# driver.net
KiCad netlist of a schematic drawn in EAGLE
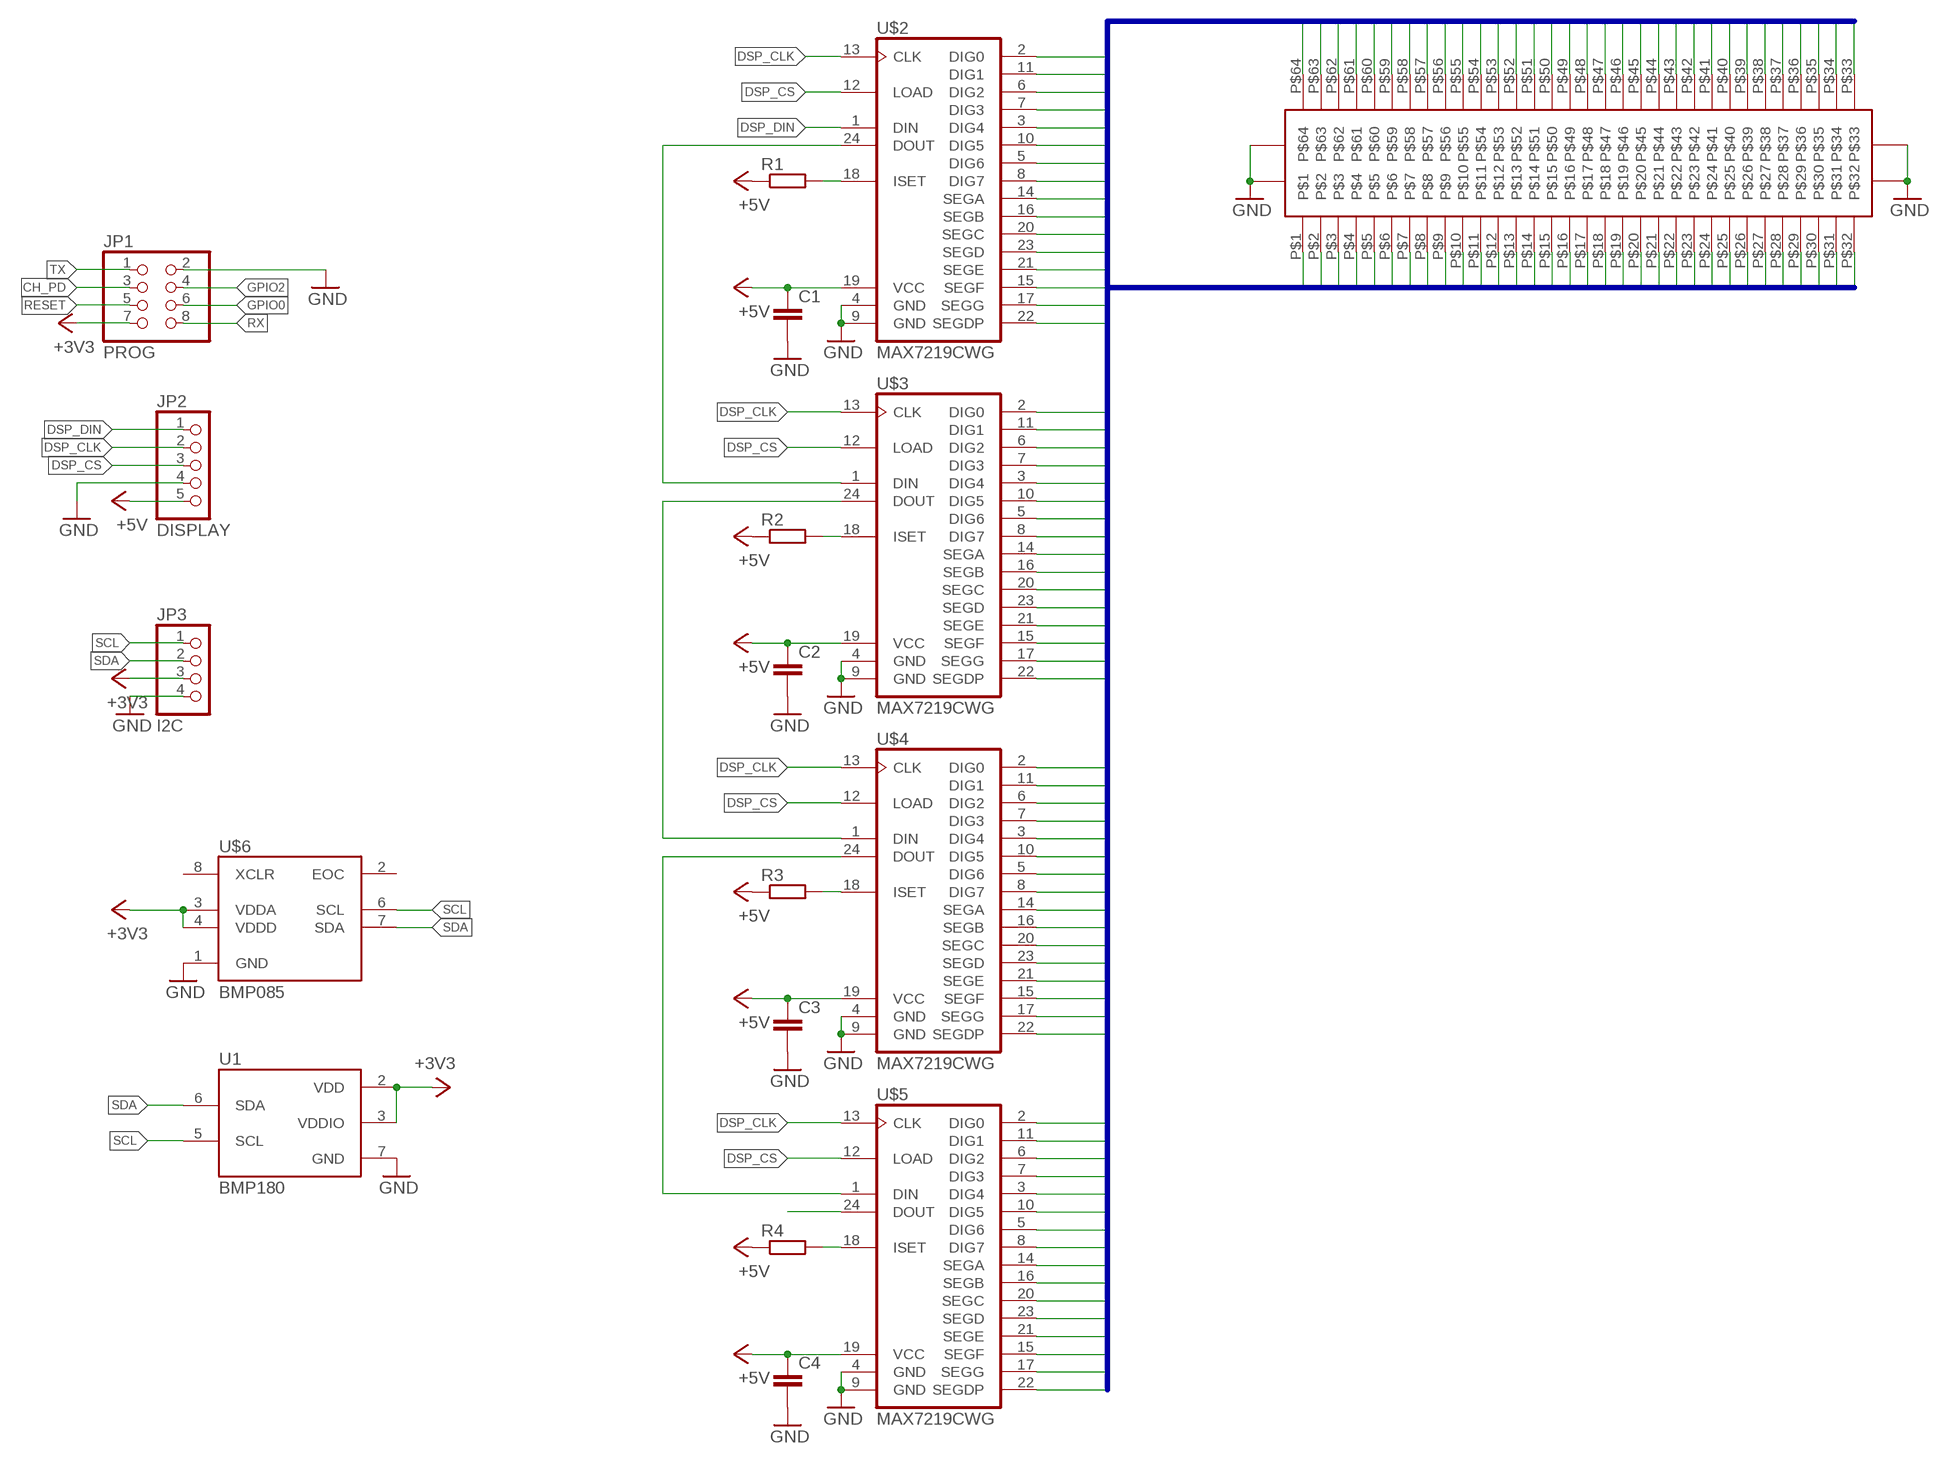
[diagram p0: schematic, sheet 1]

(export (version "E")
  (design (tool "Eeschema 10.0.6"))
  (components
    (comp (ref "C1")
      (value "C-EUC0805")
      (footprint "eagle-import:C0805")
      (libsource (lib "eagle-import") (part "C-EUC0805"))
    )
    (comp (ref "C2")
      (value "C-EUC0805")
      (footprint "eagle-import:C0805")
      (libsource (lib "eagle-import") (part "C-EUC0805"))
    )
    (comp (ref "C3")
      (value "C-EUC0805")
      (footprint "eagle-import:C0805")
      (libsource (lib "eagle-import") (part "C-EUC0805"))
    )
    (comp (ref "C4")
      (value "C-EUC0805")
      (footprint "eagle-import:C0805")
      (libsource (lib "eagle-import") (part "C-EUC0805"))
    )
    (comp (ref "JP1")
      (value "PROG")
      (footprint "eagle-import:2X04")
      (libsource (lib "eagle-import") (part "PINHD-2X4"))
    )
    (comp (ref "JP2")
      (value "DISPLAY")
      (footprint "eagle-import:1X05")
      (libsource (lib "eagle-import") (part "PINHD-1X5"))
    )
    (comp (ref "JP3")
      (value "I2C")
      (footprint "eagle-import:1X04")
      (libsource (lib "eagle-import") (part "PINHD-1X4"))
    )
    (comp (ref "R1")
      (value "R-EU_R0805")
      (footprint "eagle-import:R0805")
      (libsource (lib "eagle-import") (part "R-EU_R0805"))
    )
    (comp (ref "R2")
      (value "R-EU_R0805")
      (footprint "eagle-import:R0805")
      (libsource (lib "eagle-import") (part "R-EU_R0805"))
    )
    (comp (ref "R3")
      (value "R-EU_R0805")
      (footprint "eagle-import:R0805")
      (libsource (lib "eagle-import") (part "R-EU_R0805"))
    )
    (comp (ref "R4")
      (value "R-EU_R0805")
      (footprint "eagle-import:R0805")
      (libsource (lib "eagle-import") (part "R-EU_R0805"))
    )
    (comp (ref "U$1")
      (value "ANGLE_BOARD_CONNECTORTWO_SIDED")
      (footprint "eagle-import:TWO_SIDED")
      (libsource (lib "eagle-import") (part "ANGLE_BOARD_CONNECTORTWO_SIDED"))
    )
    (comp (ref "U$2")
      (value "MAX7219CWG")
      (footprint "eagle-import:SO24L")
      (libsource (lib "eagle-import") (part "MAX7219CWG"))
    )
    (comp (ref "U$3")
      (value "MAX7219CWG")
      (footprint "eagle-import:SO24L")
      (libsource (lib "eagle-import") (part "MAX7219CWG"))
    )
    (comp (ref "U$4")
      (value "MAX7219CWG")
      (footprint "eagle-import:SO24L")
      (libsource (lib "eagle-import") (part "MAX7219CWG"))
    )
    (comp (ref "U$5")
      (value "MAX7219CWG")
      (footprint "eagle-import:SO24L")
      (libsource (lib "eagle-import") (part "MAX7219CWG"))
    )
    (comp (ref "U$6")
      (value "BMP085")
      (footprint "eagle-import:BMP085")
      (libsource (lib "eagle-import") (part "BMP085"))
    )
    (comp (ref "U1")
      (value "BMP180")
      (footprint "eagle-import:BMP180")
      (libsource (lib "eagle-import") (part "BMP180"))
    )
  )
  (nets
    (net (code "1") (name "+3V3") (class "Default")
      (node (ref "JP1") (pin "7") (pinfunction "7_7") (pintype "passive"))
      (node (ref "JP3") (pin "3") (pinfunction "3_3") (pintype "passive"))
      (node (ref "U$6") (pin "3") (pinfunction "VDDA_3") (pintype "power_in"))
      (node (ref "U$6") (pin "4") (pinfunction "VDDD_4") (pintype "power_in"))
      (node (ref "U1") (pin "2") (pinfunction "VDD_2") (pintype "power_in"))
      (node (ref "U1") (pin "3") (pinfunction "VDDIO_3") (pintype "power_in"))
    )
    (net (code "2") (name "+5V") (class "Default")
      (node (ref "C1") (pin "1") (pinfunction "1_1") (pintype "passive"))
      (node (ref "C2") (pin "1") (pinfunction "1_1") (pintype "passive"))
      (node (ref "C3") (pin "1") (pinfunction "1_1") (pintype "passive"))
      (node (ref "C4") (pin "1") (pinfunction "1_1") (pintype "passive"))
      (node (ref "JP2") (pin "5") (pinfunction "5_5") (pintype "passive"))
      (node (ref "R1") (pin "1") (pinfunction "1_1") (pintype "passive"))
      (node (ref "R2") (pin "1") (pinfunction "1_1") (pintype "passive"))
      (node (ref "R3") (pin "1") (pinfunction "1_1") (pintype "passive"))
      (node (ref "R4") (pin "1") (pinfunction "1_1") (pintype "passive"))
      (node (ref "U$2") (pin "19") (pinfunction "VCC_19") (pintype "power_in"))
      (node (ref "U$3") (pin "19") (pinfunction "VCC_19") (pintype "power_in"))
      (node (ref "U$4") (pin "19") (pinfunction "VCC_19") (pintype "power_in"))
      (node (ref "U$5") (pin "19") (pinfunction "VCC_19") (pintype "power_in"))
    )
    (net (code "3") (name "/M1C1") (class "Default")
      (node (ref "U$1") (pin "P$64") (pinfunction "P$64_P$64") (pintype "bidirectional"))
      (node (ref "U$2") (pin "2") (pinfunction "DIG0_2") (pintype "output"))
    )
    (net (code "4") (name "/M1C2") (class "Default")
      (node (ref "U$1") (pin "P$63") (pinfunction "P$63_P$63") (pintype "bidirectional"))
      (node (ref "U$2") (pin "11") (pinfunction "DIG1_11") (pintype "output"))
    )
    (net (code "5") (name "/M1C3") (class "Default")
      (node (ref "U$1") (pin "P$62") (pinfunction "P$62_P$62") (pintype "bidirectional"))
      (node (ref "U$2") (pin "6") (pinfunction "DIG2_6") (pintype "output"))
    )
    (net (code "6") (name "/M1C4") (class "Default")
      (node (ref "U$1") (pin "P$61") (pinfunction "P$61_P$61") (pintype "bidirectional"))
      (node (ref "U$2") (pin "7") (pinfunction "DIG3_7") (pintype "output"))
    )
    (net (code "7") (name "/M1C5") (class "Default")
      (node (ref "U$1") (pin "P$60") (pinfunction "P$60_P$60") (pintype "bidirectional"))
      (node (ref "U$2") (pin "3") (pinfunction "DIG4_3") (pintype "output"))
    )
    (net (code "8") (name "/M1C6") (class "Default")
      (node (ref "U$1") (pin "P$59") (pinfunction "P$59_P$59") (pintype "bidirectional"))
      (node (ref "U$2") (pin "10") (pinfunction "DIG5_10") (pintype "output"))
    )
    (net (code "9") (name "/M1C7") (class "Default")
      (node (ref "U$1") (pin "P$58") (pinfunction "P$58_P$58") (pintype "bidirectional"))
      (node (ref "U$2") (pin "5") (pinfunction "DIG6_5") (pintype "output"))
    )
    (net (code "10") (name "/M1C8") (class "Default")
      (node (ref "U$1") (pin "P$57") (pinfunction "P$57_P$57") (pintype "bidirectional"))
      (node (ref "U$2") (pin "8") (pinfunction "DIG7_8") (pintype "output"))
    )
    (net (code "11") (name "/M1R1") (class "Default")
      (node (ref "U$1") (pin "P$1") (pinfunction "P$1_P$1") (pintype "bidirectional"))
      (node (ref "U$2") (pin "14") (pinfunction "SEGA_14") (pintype "output"))
    )
    (net (code "12") (name "/M1R2") (class "Default")
      (node (ref "U$1") (pin "P$2") (pinfunction "P$2_P$2") (pintype "bidirectional"))
      (node (ref "U$2") (pin "16") (pinfunction "SEGB_16") (pintype "output"))
    )
    (net (code "13") (name "/M1R3") (class "Default")
      (node (ref "U$1") (pin "P$3") (pinfunction "P$3_P$3") (pintype "bidirectional"))
      (node (ref "U$2") (pin "20") (pinfunction "SEGC_20") (pintype "output"))
    )
    (net (code "14") (name "/M1R4") (class "Default")
      (node (ref "U$1") (pin "P$4") (pinfunction "P$4_P$4") (pintype "bidirectional"))
      (node (ref "U$2") (pin "23") (pinfunction "SEGD_23") (pintype "output"))
    )
    (net (code "15") (name "/M1R5") (class "Default")
      (node (ref "U$1") (pin "P$5") (pinfunction "P$5_P$5") (pintype "bidirectional"))
      (node (ref "U$2") (pin "21") (pinfunction "SEGE_21") (pintype "output"))
    )
    (net (code "16") (name "/M1R6") (class "Default")
      (node (ref "U$1") (pin "P$6") (pinfunction "P$6_P$6") (pintype "bidirectional"))
      (node (ref "U$2") (pin "15") (pinfunction "SEGF_15") (pintype "output"))
    )
    (net (code "17") (name "/M1R7") (class "Default")
      (node (ref "U$1") (pin "P$7") (pinfunction "P$7_P$7") (pintype "bidirectional"))
      (node (ref "U$2") (pin "17") (pinfunction "SEGG_17") (pintype "output"))
    )
    (net (code "18") (name "/M1R8") (class "Default")
      (node (ref "U$1") (pin "P$8") (pinfunction "P$8_P$8") (pintype "bidirectional"))
      (node (ref "U$2") (pin "22") (pinfunction "SEGDP_22") (pintype "output"))
    )
    (net (code "19") (name "/M2C1") (class "Default")
      (node (ref "U$1") (pin "P$56") (pinfunction "P$56_P$56") (pintype "bidirectional"))
      (node (ref "U$3") (pin "2") (pinfunction "DIG0_2") (pintype "output"))
    )
    (net (code "20") (name "/M2C2") (class "Default")
      (node (ref "U$1") (pin "P$55") (pinfunction "P$55_P$55") (pintype "bidirectional"))
      (node (ref "U$3") (pin "11") (pinfunction "DIG1_11") (pintype "output"))
    )
    (net (code "21") (name "/M2C3") (class "Default")
      (node (ref "U$1") (pin "P$54") (pinfunction "P$54_P$54") (pintype "bidirectional"))
      (node (ref "U$3") (pin "6") (pinfunction "DIG2_6") (pintype "output"))
    )
    (net (code "22") (name "/M2C4") (class "Default")
      (node (ref "U$1") (pin "P$53") (pinfunction "P$53_P$53") (pintype "bidirectional"))
      (node (ref "U$3") (pin "7") (pinfunction "DIG3_7") (pintype "output"))
    )
    (net (code "23") (name "/M2C5") (class "Default")
      (node (ref "U$1") (pin "P$52") (pinfunction "P$52_P$52") (pintype "bidirectional"))
      (node (ref "U$3") (pin "3") (pinfunction "DIG4_3") (pintype "output"))
    )
    (net (code "24") (name "/M2C6") (class "Default")
      (node (ref "U$1") (pin "P$51") (pinfunction "P$51_P$51") (pintype "bidirectional"))
      (node (ref "U$3") (pin "10") (pinfunction "DIG5_10") (pintype "output"))
    )
    (net (code "25") (name "/M2C7") (class "Default")
      (node (ref "U$1") (pin "P$50") (pinfunction "P$50_P$50") (pintype "bidirectional"))
      (node (ref "U$3") (pin "5") (pinfunction "DIG6_5") (pintype "output"))
    )
    (net (code "26") (name "/M2C8") (class "Default")
      (node (ref "U$1") (pin "P$49") (pinfunction "P$49_P$49") (pintype "bidirectional"))
      (node (ref "U$3") (pin "8") (pinfunction "DIG7_8") (pintype "output"))
    )
    (net (code "27") (name "/M2R1") (class "Default")
      (node (ref "U$1") (pin "P$9") (pinfunction "P$9_P$9") (pintype "bidirectional"))
      (node (ref "U$3") (pin "14") (pinfunction "SEGA_14") (pintype "output"))
    )
    (net (code "28") (name "/M2R2") (class "Default")
      (node (ref "U$1") (pin "P$10") (pinfunction "P$10_P$10") (pintype "bidirectional"))
      (node (ref "U$3") (pin "16") (pinfunction "SEGB_16") (pintype "output"))
    )
    (net (code "29") (name "/M2R3") (class "Default")
      (node (ref "U$1") (pin "P$11") (pinfunction "P$11_P$11") (pintype "bidirectional"))
      (node (ref "U$3") (pin "20") (pinfunction "SEGC_20") (pintype "output"))
    )
    (net (code "30") (name "/M2R4") (class "Default")
      (node (ref "U$1") (pin "P$12") (pinfunction "P$12_P$12") (pintype "bidirectional"))
      (node (ref "U$3") (pin "23") (pinfunction "SEGD_23") (pintype "output"))
    )
    (net (code "31") (name "/M2R5") (class "Default")
      (node (ref "U$1") (pin "P$13") (pinfunction "P$13_P$13") (pintype "bidirectional"))
      (node (ref "U$3") (pin "21") (pinfunction "SEGE_21") (pintype "output"))
    )
    (net (code "32") (name "/M2R6") (class "Default")
      (node (ref "U$1") (pin "P$14") (pinfunction "P$14_P$14") (pintype "bidirectional"))
      (node (ref "U$3") (pin "15") (pinfunction "SEGF_15") (pintype "output"))
    )
    (net (code "33") (name "/M2R7") (class "Default")
      (node (ref "U$1") (pin "P$15") (pinfunction "P$15_P$15") (pintype "bidirectional"))
      (node (ref "U$3") (pin "17") (pinfunction "SEGG_17") (pintype "output"))
    )
    (net (code "34") (name "/M2R8") (class "Default")
      (node (ref "U$1") (pin "P$16") (pinfunction "P$16_P$16") (pintype "bidirectional"))
      (node (ref "U$3") (pin "22") (pinfunction "SEGDP_22") (pintype "output"))
    )
    (net (code "35") (name "/M3C1") (class "Default")
      (node (ref "U$1") (pin "P$48") (pinfunction "P$48_P$48") (pintype "bidirectional"))
      (node (ref "U$4") (pin "2") (pinfunction "DIG0_2") (pintype "output"))
    )
    (net (code "36") (name "/M3C2") (class "Default")
      (node (ref "U$1") (pin "P$47") (pinfunction "P$47_P$47") (pintype "bidirectional"))
      (node (ref "U$4") (pin "11") (pinfunction "DIG1_11") (pintype "output"))
    )
    (net (code "37") (name "/M3C3") (class "Default")
      (node (ref "U$1") (pin "P$46") (pinfunction "P$46_P$46") (pintype "bidirectional"))
      (node (ref "U$4") (pin "6") (pinfunction "DIG2_6") (pintype "output"))
    )
    (net (code "38") (name "/M3C4") (class "Default")
      (node (ref "U$1") (pin "P$45") (pinfunction "P$45_P$45") (pintype "bidirectional"))
      (node (ref "U$4") (pin "7") (pinfunction "DIG3_7") (pintype "output"))
    )
    (net (code "39") (name "/M3C5") (class "Default")
      (node (ref "U$1") (pin "P$44") (pinfunction "P$44_P$44") (pintype "bidirectional"))
      (node (ref "U$4") (pin "3") (pinfunction "DIG4_3") (pintype "output"))
    )
    (net (code "40") (name "/M3C6") (class "Default")
      (node (ref "U$1") (pin "P$43") (pinfunction "P$43_P$43") (pintype "bidirectional"))
      (node (ref "U$4") (pin "10") (pinfunction "DIG5_10") (pintype "output"))
    )
    (net (code "41") (name "/M3C7") (class "Default")
      (node (ref "U$1") (pin "P$42") (pinfunction "P$42_P$42") (pintype "bidirectional"))
      (node (ref "U$4") (pin "5") (pinfunction "DIG6_5") (pintype "output"))
    )
    (net (code "42") (name "/M3C8") (class "Default")
      (node (ref "U$1") (pin "P$41") (pinfunction "P$41_P$41") (pintype "bidirectional"))
      (node (ref "U$4") (pin "8") (pinfunction "DIG7_8") (pintype "output"))
    )
    (net (code "43") (name "/M3R1") (class "Default")
      (node (ref "U$1") (pin "P$17") (pinfunction "P$17_P$17") (pintype "bidirectional"))
      (node (ref "U$4") (pin "14") (pinfunction "SEGA_14") (pintype "output"))
    )
    (net (code "44") (name "/M3R2") (class "Default")
      (node (ref "U$1") (pin "P$18") (pinfunction "P$18_P$18") (pintype "bidirectional"))
      (node (ref "U$4") (pin "16") (pinfunction "SEGB_16") (pintype "output"))
    )
    (net (code "45") (name "/M3R3") (class "Default")
      (node (ref "U$1") (pin "P$19") (pinfunction "P$19_P$19") (pintype "bidirectional"))
      (node (ref "U$4") (pin "20") (pinfunction "SEGC_20") (pintype "output"))
    )
    (net (code "46") (name "/M3R4") (class "Default")
      (node (ref "U$1") (pin "P$20") (pinfunction "P$20_P$20") (pintype "bidirectional"))
      (node (ref "U$4") (pin "23") (pinfunction "SEGD_23") (pintype "output"))
    )
    (net (code "47") (name "/M3R5") (class "Default")
      (node (ref "U$1") (pin "P$21") (pinfunction "P$21_P$21") (pintype "bidirectional"))
      (node (ref "U$4") (pin "21") (pinfunction "SEGE_21") (pintype "output"))
    )
    (net (code "48") (name "/M3R6") (class "Default")
      (node (ref "U$1") (pin "P$22") (pinfunction "P$22_P$22") (pintype "bidirectional"))
      (node (ref "U$4") (pin "15") (pinfunction "SEGF_15") (pintype "output"))
    )
    (net (code "49") (name "/M3R7") (class "Default")
      (node (ref "U$1") (pin "P$23") (pinfunction "P$23_P$23") (pintype "bidirectional"))
      (node (ref "U$4") (pin "17") (pinfunction "SEGG_17") (pintype "output"))
    )
    (net (code "50") (name "/M3R8") (class "Default")
      (node (ref "U$1") (pin "P$24") (pinfunction "P$24_P$24") (pintype "bidirectional"))
      (node (ref "U$4") (pin "22") (pinfunction "SEGDP_22") (pintype "output"))
    )
    (net (code "51") (name "/M4C1") (class "Default")
      (node (ref "U$1") (pin "P$40") (pinfunction "P$40_P$40") (pintype "bidirectional"))
      (node (ref "U$5") (pin "2") (pinfunction "DIG0_2") (pintype "output"))
    )
    (net (code "52") (name "/M4C2") (class "Default")
      (node (ref "U$1") (pin "P$39") (pinfunction "P$39_P$39") (pintype "bidirectional"))
      (node (ref "U$5") (pin "11") (pinfunction "DIG1_11") (pintype "output"))
    )
    (net (code "53") (name "/M4C3") (class "Default")
      (node (ref "U$1") (pin "P$38") (pinfunction "P$38_P$38") (pintype "bidirectional"))
      (node (ref "U$5") (pin "6") (pinfunction "DIG2_6") (pintype "output"))
    )
    (net (code "54") (name "/M4C4") (class "Default")
      (node (ref "U$1") (pin "P$37") (pinfunction "P$37_P$37") (pintype "bidirectional"))
      (node (ref "U$5") (pin "7") (pinfunction "DIG3_7") (pintype "output"))
    )
    (net (code "55") (name "/M4C5") (class "Default")
      (node (ref "U$1") (pin "P$36") (pinfunction "P$36_P$36") (pintype "bidirectional"))
      (node (ref "U$5") (pin "3") (pinfunction "DIG4_3") (pintype "output"))
    )
    (net (code "56") (name "/M4C6") (class "Default")
      (node (ref "U$1") (pin "P$35") (pinfunction "P$35_P$35") (pintype "bidirectional"))
      (node (ref "U$5") (pin "10") (pinfunction "DIG5_10") (pintype "output"))
    )
    (net (code "57") (name "/M4C7") (class "Default")
      (node (ref "U$1") (pin "P$34") (pinfunction "P$34_P$34") (pintype "bidirectional"))
      (node (ref "U$5") (pin "5") (pinfunction "DIG6_5") (pintype "output"))
    )
    (net (code "58") (name "/M4C8") (class "Default")
      (node (ref "U$1") (pin "P$33") (pinfunction "P$33_P$33") (pintype "bidirectional"))
      (node (ref "U$5") (pin "8") (pinfunction "DIG7_8") (pintype "output"))
    )
    (net (code "59") (name "/M4R1") (class "Default")
      (node (ref "U$1") (pin "P$25") (pinfunction "P$25_P$25") (pintype "bidirectional"))
      (node (ref "U$5") (pin "14") (pinfunction "SEGA_14") (pintype "output"))
    )
    (net (code "60") (name "/M4R2") (class "Default")
      (node (ref "U$1") (pin "P$26") (pinfunction "P$26_P$26") (pintype "bidirectional"))
      (node (ref "U$5") (pin "16") (pinfunction "SEGB_16") (pintype "output"))
    )
    (net (code "61") (name "/M4R3") (class "Default")
      (node (ref "U$1") (pin "P$27") (pinfunction "P$27_P$27") (pintype "bidirectional"))
      (node (ref "U$5") (pin "20") (pinfunction "SEGC_20") (pintype "output"))
    )
    (net (code "62") (name "/M4R4") (class "Default")
      (node (ref "U$1") (pin "P$28") (pinfunction "P$28_P$28") (pintype "bidirectional"))
      (node (ref "U$5") (pin "23") (pinfunction "SEGD_23") (pintype "output"))
    )
    (net (code "63") (name "/M4R5") (class "Default")
      (node (ref "U$1") (pin "P$29") (pinfunction "P$29_P$29") (pintype "bidirectional"))
      (node (ref "U$5") (pin "21") (pinfunction "SEGE_21") (pintype "output"))
    )
    (net (code "64") (name "/M4R6") (class "Default")
      (node (ref "U$1") (pin "P$30") (pinfunction "P$30_P$30") (pintype "bidirectional"))
      (node (ref "U$5") (pin "15") (pinfunction "SEGF_15") (pintype "output"))
    )
    (net (code "65") (name "/M4R7") (class "Default")
      (node (ref "U$1") (pin "P$31") (pinfunction "P$31_P$31") (pintype "bidirectional"))
      (node (ref "U$5") (pin "17") (pinfunction "SEGG_17") (pintype "output"))
    )
    (net (code "66") (name "/M4R8") (class "Default")
      (node (ref "U$1") (pin "P$32") (pinfunction "P$32_P$32") (pintype "bidirectional"))
      (node (ref "U$5") (pin "22") (pinfunction "SEGDP_22") (pintype "output"))
    )
    (net (code "67") (name "CH_PD") (class "Default")
      (node (ref "JP1") (pin "3") (pinfunction "3_3") (pintype "passive"))
    )
    (net (code "68") (name "DSP_CLK") (class "Default")
      (node (ref "JP2") (pin "2") (pinfunction "2_2") (pintype "passive"))
      (node (ref "U$2") (pin "13") (pinfunction "CLK_13") (pintype "input"))
      (node (ref "U$3") (pin "13") (pinfunction "CLK_13") (pintype "input"))
      (node (ref "U$4") (pin "13") (pinfunction "CLK_13") (pintype "input"))
      (node (ref "U$5") (pin "13") (pinfunction "CLK_13") (pintype "input"))
    )
    (net (code "69") (name "DSP_CS") (class "Default")
      (node (ref "JP2") (pin "3") (pinfunction "3_3") (pintype "passive"))
      (node (ref "U$2") (pin "12") (pinfunction "LOAD_12") (pintype "input"))
      (node (ref "U$3") (pin "12") (pinfunction "LOAD_12") (pintype "input"))
      (node (ref "U$4") (pin "12") (pinfunction "LOAD_12") (pintype "input"))
      (node (ref "U$5") (pin "12") (pinfunction "LOAD_12") (pintype "input"))
    )
    (net (code "70") (name "DSP_DIN") (class "Default")
      (node (ref "JP2") (pin "1") (pinfunction "1_1") (pintype "passive"))
      (node (ref "U$2") (pin "1") (pinfunction "DIN_1") (pintype "input"))
    )
    (net (code "71") (name "GND") (class "Default")
      (node (ref "C1") (pin "2") (pinfunction "2_2") (pintype "passive"))
      (node (ref "C2") (pin "2") (pinfunction "2_2") (pintype "passive"))
      (node (ref "C3") (pin "2") (pinfunction "2_2") (pintype "passive"))
      (node (ref "C4") (pin "2") (pinfunction "2_2") (pintype "passive"))
      (node (ref "JP1") (pin "2") (pinfunction "2_2") (pintype "passive"))
      (node (ref "JP2") (pin "4") (pinfunction "4_4") (pintype "passive"))
      (node (ref "JP3") (pin "4") (pinfunction "4_4") (pintype "passive"))
      (node (ref "U$1") (pin "GND@1") (pinfunction "GND_GND@1") (pintype "bidirectional"))
      (node (ref "U$1") (pin "GND@2") (pinfunction "GND_GND@2") (pintype "bidirectional"))
      (node (ref "U$1") (pin "GND@3") (pinfunction "GND_GND@3") (pintype "bidirectional"))
      (node (ref "U$1") (pin "GND@4") (pinfunction "GND_GND@4") (pintype "bidirectional"))
      (node (ref "U$2") (pin "4") (pinfunction "GND_4") (pintype "power_in"))
      (node (ref "U$2") (pin "9") (pinfunction "GND_9") (pintype "power_in"))
      (node (ref "U$3") (pin "4") (pinfunction "GND_4") (pintype "power_in"))
      (node (ref "U$3") (pin "9") (pinfunction "GND_9") (pintype "power_in"))
      (node (ref "U$4") (pin "4") (pinfunction "GND_4") (pintype "power_in"))
      (node (ref "U$4") (pin "9") (pinfunction "GND_9") (pintype "power_in"))
      (node (ref "U$5") (pin "4") (pinfunction "GND_4") (pintype "power_in"))
      (node (ref "U$5") (pin "9") (pinfunction "GND_9") (pintype "power_in"))
      (node (ref "U$6") (pin "1") (pinfunction "GND_1") (pintype "power_in"))
      (node (ref "U1") (pin "7") (pinfunction "GND_7") (pintype "power_in"))
    )
    (net (code "72") (name "GPIO0") (class "Default")
      (node (ref "JP1") (pin "6") (pinfunction "6_6") (pintype "passive"))
    )
    (net (code "73") (name "GPIO2") (class "Default")
      (node (ref "JP1") (pin "4") (pinfunction "4_4") (pintype "passive"))
    )
    (net (code "74") (name "Net-(U$2-DOUT)") (class "Default")
      (node (ref "U$2") (pin "24") (pinfunction "DOUT_24") (pintype "output"))
      (node (ref "U$3") (pin "1") (pinfunction "DIN_1") (pintype "input"))
    )
    (net (code "75") (name "Net-(U$2-ISET)") (class "Default")
      (node (ref "R1") (pin "2") (pinfunction "2_2") (pintype "passive"))
      (node (ref "U$2") (pin "18") (pinfunction "ISET_18") (pintype "input"))
    )
    (net (code "76") (name "Net-(U$3-DOUT)") (class "Default")
      (node (ref "U$3") (pin "24") (pinfunction "DOUT_24") (pintype "output"))
      (node (ref "U$4") (pin "1") (pinfunction "DIN_1") (pintype "input"))
    )
    (net (code "77") (name "Net-(U$3-ISET)") (class "Default")
      (node (ref "R2") (pin "2") (pinfunction "2_2") (pintype "passive"))
      (node (ref "U$3") (pin "18") (pinfunction "ISET_18") (pintype "input"))
    )
    (net (code "78") (name "Net-(U$4-DOUT)") (class "Default")
      (node (ref "U$4") (pin "24") (pinfunction "DOUT_24") (pintype "output"))
      (node (ref "U$5") (pin "1") (pinfunction "DIN_1") (pintype "input"))
    )
    (net (code "79") (name "Net-(U$4-ISET)") (class "Default")
      (node (ref "R3") (pin "2") (pinfunction "2_2") (pintype "passive"))
      (node (ref "U$4") (pin "18") (pinfunction "ISET_18") (pintype "input"))
    )
    (net (code "80") (name "Net-(U$5-ISET)") (class "Default")
      (node (ref "R4") (pin "2") (pinfunction "2_2") (pintype "passive"))
      (node (ref "U$5") (pin "18") (pinfunction "ISET_18") (pintype "input"))
    )
    (net (code "81") (name "RESET") (class "Default")
      (node (ref "JP1") (pin "5") (pinfunction "5_5") (pintype "passive"))
    )
    (net (code "82") (name "RX") (class "Default")
      (node (ref "JP1") (pin "8") (pinfunction "8_8") (pintype "passive"))
    )
    (net (code "83") (name "SCL") (class "Default")
      (node (ref "JP3") (pin "1") (pinfunction "1_1") (pintype "passive"))
      (node (ref "U$6") (pin "6") (pinfunction "SCL_6") (pintype "input"))
      (node (ref "U1") (pin "5") (pinfunction "SCL_5") (pintype "input"))
    )
    (net (code "84") (name "SDA") (class "Default")
      (node (ref "JP3") (pin "2") (pinfunction "2_2") (pintype "passive"))
      (node (ref "U$6") (pin "7") (pinfunction "SDA_7") (pintype "bidirectional"))
      (node (ref "U1") (pin "6") (pinfunction "SDA_6") (pintype "bidirectional"))
    )
    (net (code "85") (name "TX") (class "Default")
      (node (ref "JP1") (pin "1") (pinfunction "1_1") (pintype "passive"))
    )
    (net (code "86") (name "unconnected-(U$5-DOUT-Pad24)") (class "Default")
      (node (ref "U$5") (pin "24") (pinfunction "DOUT_24") (pintype "output"))
    )
    (net (code "87") (name "unconnected-(U$6-EOC-Pad2)") (class "Default")
      (node (ref "U$6") (pin "2") (pinfunction "EOC_2") (pintype "output"))
    )
    (net (code "88") (name "unconnected-(U$6-NC-Pad5)") (class "Default")
      (node (ref "U$6") (pin "5") (pinfunction "NC_5") (pintype "no_connect"))
    )
    (net (code "89") (name "unconnected-(U$6-XCLR-Pad8)") (class "Default")
      (node (ref "U$6") (pin "8") (pinfunction "XCLR_8") (pintype "input"))
    )
  )
)
